# open-lab-mon-A-mini.net
KiCad netlist of a schematic drawn in EAGLE
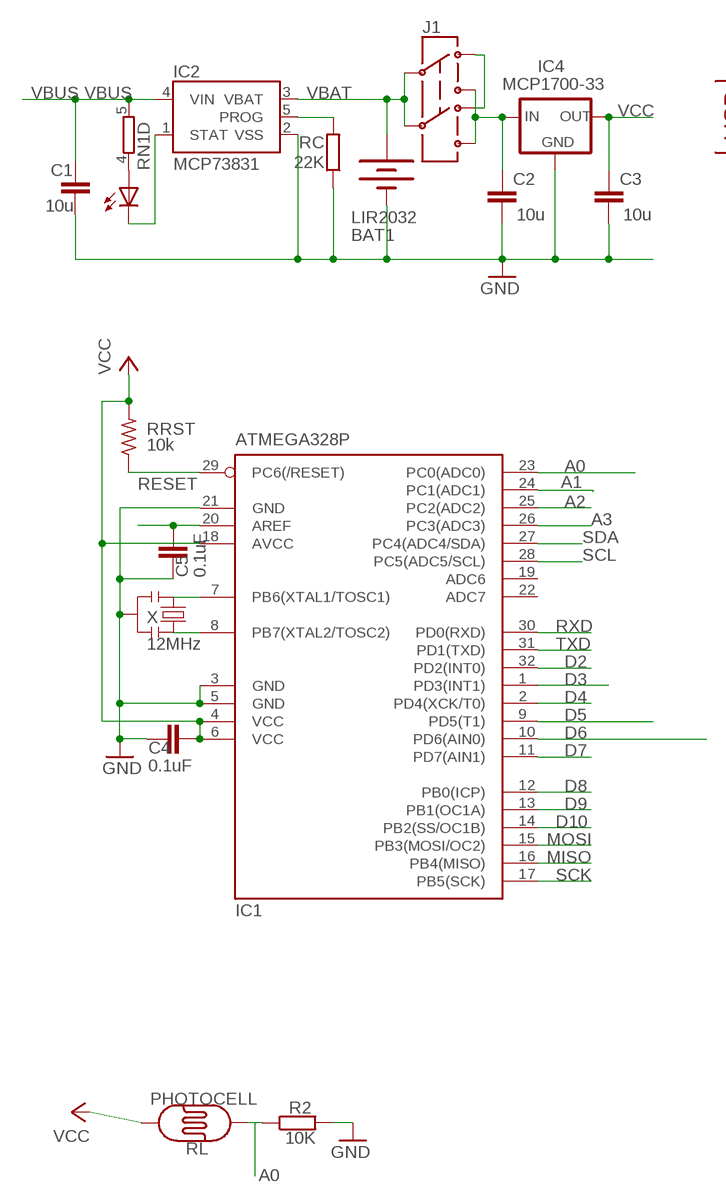
[diagram p0: schematic, sheet 1, part 1 of 2]
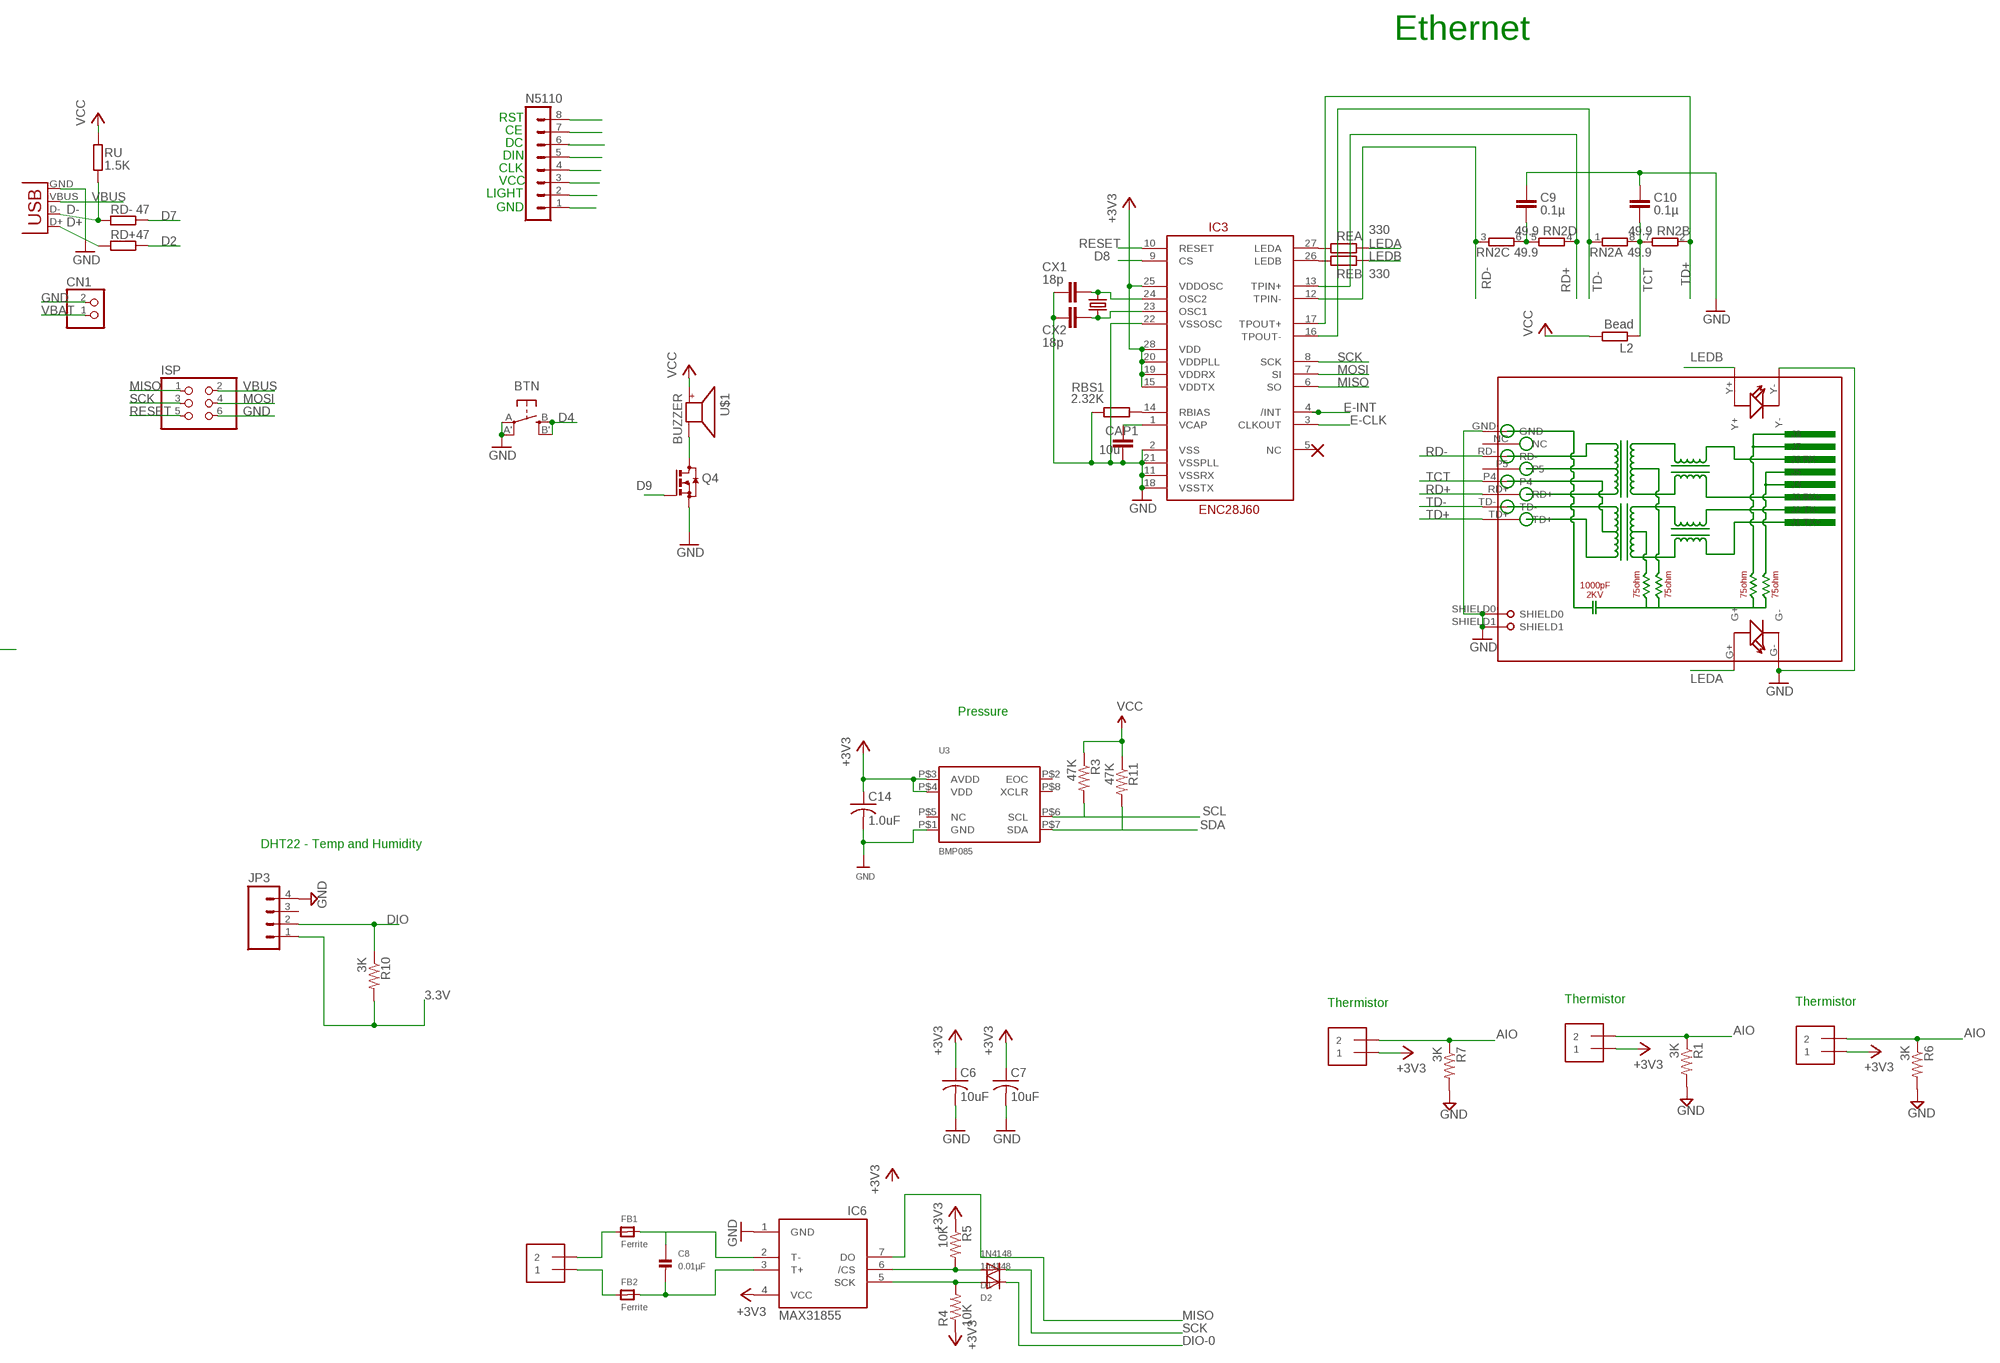
[diagram p1: schematic, sheet 1, part 2 of 2]

(export (version "E")
  (design (tool "Eeschema 10.0.6"))
  (components
    (comp (ref "BAT1")
      (value "LIR2032")
      (footprint "eagle-import:BATTCOM_20MM_PTH_SMT")
      (libsource (lib "eagle-import") (part "BATTERYBATTCOM_20MM_PTH_SMT"))
    )
    (comp (ref "BTN")
      (value "EVQQ2")
      (footprint "eagle-import:EVQ-Q2")
      (libsource (lib "eagle-import") (part "EVQQ2"))
    )
    (comp (ref "C1")
      (value "10u")
      (footprint "eagle-import:C0805")
      (libsource (lib "eagle-import") (part "resistor_C-EUC0805"))
    )
    (comp (ref "C2")
      (value "10u")
      (footprint "eagle-import:C0805")
      (libsource (lib "eagle-import") (part "resistor_C-EUC0805"))
    )
    (comp (ref "C3")
      (value "10u")
      (footprint "eagle-import:C0805")
      (libsource (lib "eagle-import") (part "resistor_C-EUC0805"))
    )
    (comp (ref "C4")
      (value "0.1uF")
      (footprint "eagle-import:C0805")
      (libsource (lib "eagle-import") (part "C-EUC0805"))
    )
    (comp (ref "C5")
      (value "0.1uF")
      (footprint "eagle-import:C0805")
      (libsource (lib "eagle-import") (part "C-EUC0805"))
    )
    (comp (ref "C6")
      (value "10uF")
      (footprint "eagle-import:C0805K")
      (libsource (lib "eagle-import") (part "C-USC0805K"))
    )
    (comp (ref "C7")
      (value "10uF")
      (footprint "eagle-import:C0805K")
      (libsource (lib "eagle-import") (part "C-USC0805K"))
    )
    (comp (ref "C8")
      (value "0.01µF")
      (footprint "eagle-import:_0805")
      (libsource (lib "eagle-import") (part "CAP_CERAMIC_0805"))
    )
    (comp (ref "C9")
      (value "0.1µ")
      (footprint "eagle-import:C0805")
      (libsource (lib "eagle-import") (part "resistor_C-EUC0805"))
    )
    (comp (ref "C10")
      (value "0.1µ")
      (footprint "eagle-import:C0805")
      (libsource (lib "eagle-import") (part "resistor_C-EUC0805"))
    )
    (comp (ref "C14")
      (value "1.0uF")
      (footprint "eagle-import:C0805")
      (libsource (lib "eagle-import") (part "C-USC0805"))
    )
    (comp (ref "CAP1")
      (value "10u")
      (footprint "eagle-import:C0805")
      (libsource (lib "eagle-import") (part "resistor_C-EUC0805"))
    )
    (comp (ref "CHG")
      (value "0805")
      (footprint "eagle-import:CHIPLED_0805")
      (libsource (lib "eagle-import") (part "LEDCHIPLED_0805"))
    )
    (comp (ref "CN1")
      (value "JST_2PIN-SMT-RA")
      (footprint "eagle-import:JST-PH-2-SMT-RA")
      (libsource (lib "eagle-import") (part "JST_2PIN-SMT-RA"))
    )
    (comp (ref "CX1")
      (value "18p")
      (footprint "eagle-import:C0805")
      (libsource (lib "eagle-import") (part "resistor_C-EUC0805"))
    )
    (comp (ref "CX2")
      (value "18p")
      (footprint "eagle-import:C0805")
      (libsource (lib "eagle-import") (part "resistor_C-EUC0805"))
    )
    (comp (ref "D1")
      (value "1N4148")
      (footprint "eagle-import:SOD-323F")
      (libsource (lib "eagle-import") (part "DIODESOD-323F"))
    )
    (comp (ref "D2")
      (value "1n4148")
      (footprint "eagle-import:SOD-323F")
      (libsource (lib "eagle-import") (part "DIODESOD-323F"))
    )
    (comp (ref "FB1")
      (value "Ferrite")
      (footprint "eagle-import:_0805")
      (libsource (lib "eagle-import") (part "FERRITE_0805"))
    )
    (comp (ref "FB2")
      (value "Ferrite")
      (footprint "eagle-import:_0805")
      (libsource (lib "eagle-import") (part "FERRITE_0805"))
    )
    (comp (ref "IC1")
      (value "ATMEGA328P")
      (footprint "eagle-import:TQFP32-08")
      (fields (field (name "MPN") "ATMEGA8-16AU"))
      (libsource (lib "eagle-import") (part "MEGA8-AI"))
    )
    (comp (ref "IC2")
      (value "MCP73831")
      (footprint "eagle-import:SOT23-5")
      (libsource (lib "eagle-import") (part "MCP73831"))
    )
    (comp (ref "IC3")
      (value "ENC28J60")
      (footprint "eagle-import:SOIC28WLONG")
      (libsource (lib "eagle-import") (part "ENC28J60SO28LONG"))
    )
    (comp (ref "IC4")
      (value "MCP1700-33")
      (footprint "eagle-import:SOT23")
      (libsource (lib "eagle-import") (part "MCP1700SOT233"))
    )
    (comp (ref "IC6")
      (value "MAX31855")
      (footprint "eagle-import:SO08")
      (libsource (lib "eagle-import") (part "MAX6675"))
    )
    (comp (ref "ISP")
      (value "PINHD-2X3")
      (footprint "eagle-import:2X03")
      (libsource (lib "eagle-import") (part "PINHD-2X3"))
    )
    (comp (ref "J1")
      (value "AYZ0202")
      (footprint "eagle-import:AYZ0202")
      (libsource (lib "eagle-import") (part "AYZ0202"))
    )
    (comp (ref "J2")
      (value "1X2-3.5MM")
      (footprint "eagle-import:1X2-3.5MM")
      (libsource (lib "eagle-import") (part "1X2-3.5MM"))
    )
    (comp (ref "J3")
      (value "1X2-3.5MM")
      (footprint "eagle-import:1X2-3.5MM")
      (libsource (lib "eagle-import") (part "1X2-3.5MM"))
    )
    (comp (ref "J4")
      (value "1X2-3.5MM")
      (footprint "eagle-import:1X2-3.5MM")
      (libsource (lib "eagle-import") (part "1X2-3.5MM"))
    )
    (comp (ref "J5")
      (value "1X2-3.5MM")
      (footprint "eagle-import:1X2-3.5MM")
      (libsource (lib "eagle-import") (part "1X2-3.5MM"))
    )
    (comp (ref "JP3")
      (value "M04LOCK")
      (footprint "eagle-import:1X04_LOCK")
      (libsource (lib "eagle-import") (part "M04LOCK"))
    )
    (comp (ref "L2")
      (value "Bead")
      (footprint "eagle-import:R0805")
      (libsource (lib "eagle-import") (part "R-EU_R0805"))
    )
    (comp (ref "N5110")
      (value "MA08-1")
      (footprint "eagle-import:MA08-1")
      (libsource (lib "eagle-import") (part "MA08-1"))
    )
    (comp (ref "Q4")
      (value "BSS123")
      (footprint "eagle-import:SOT23")
      (libsource (lib "eagle-import") (part "BSS123"))
    )
    (comp (ref "R1")
      (value "3K")
      (footprint "eagle-import:R0805")
      (libsource (lib "eagle-import") (part "R-US_R0805"))
    )
    (comp (ref "R2")
      (value "10K")
      (footprint "eagle-import:R0805")
      (libsource (lib "eagle-import") (part "R-EU_R0805"))
    )
    (comp (ref "R3")
      (value "47K")
      (footprint "eagle-import:R0805")
      (libsource (lib "eagle-import") (part "R-US_R0805"))
    )
    (comp (ref "R4")
      (value "10K")
      (footprint "eagle-import:R0805")
      (libsource (lib "eagle-import") (part "R-US_R0805"))
    )
    (comp (ref "R5")
      (value "10K")
      (footprint "eagle-import:R0805")
      (libsource (lib "eagle-import") (part "R-US_R0805"))
    )
    (comp (ref "R6")
      (value "3K")
      (footprint "eagle-import:R0805")
      (libsource (lib "eagle-import") (part "R-US_R0805"))
    )
    (comp (ref "R7")
      (value "3K")
      (footprint "eagle-import:R0805")
      (libsource (lib "eagle-import") (part "R-US_R0805"))
    )
    (comp (ref "R10")
      (value "3K")
      (footprint "eagle-import:R0805")
      (libsource (lib "eagle-import") (part "R-US_R0805"))
    )
    (comp (ref "R11")
      (value "47K")
      (footprint "eagle-import:R0805")
      (libsource (lib "eagle-import") (part "R-US_R0805"))
    )
    (comp (ref "RBS1")
      (value "2.32K")
      (footprint "eagle-import:R0805")
      (libsource (lib "eagle-import") (part "R-EU_R0805"))
    )
    (comp (ref "RC")
      (value "22K")
      (footprint "eagle-import:R0805")
      (libsource (lib "eagle-import") (part "R-EU_R0805"))
    )
    (comp (ref "RD+")
      (value "47")
      (footprint "eagle-import:R0805")
      (libsource (lib "eagle-import") (part "R-EU_R0805"))
    )
    (comp (ref "RD-")
      (value "47")
      (footprint "eagle-import:R0805")
      (libsource (lib "eagle-import") (part "R-EU_R0805"))
    )
    (comp (ref "REA")
      (value "330")
      (footprint "eagle-import:R0805")
      (libsource (lib "eagle-import") (part "R-EU_R0805"))
    )
    (comp (ref "REB")
      (value "330")
      (footprint "eagle-import:R0805")
      (libsource (lib "eagle-import") (part "R-EU_R0805"))
    )
    (comp (ref "RJ1")
      (value "HR911105A")
      (footprint "eagle-import:HR911105A")
      (libsource (lib "eagle-import") (part "HR911105A"))
    )
    (comp (ref "RL")
      (value "PHOTOCELL")
      (footprint "eagle-import:PHOTOCELL")
      (libsource (lib "eagle-import") (part "PHOTOCELLPTH"))
    )
    (comp (ref "RN1")
      (value "4R-NEXB38V")
      (footprint "eagle-import:EXB38V")
      (libsource (lib "eagle-import") (part "4R-NEXB38V"))
    )
    (comp (ref "RN2")
      (value "49.9")
      (footprint "eagle-import:EXB38V")
      (libsource (lib "eagle-import") (part "4R-NEXB38V"))
    )
    (comp (ref "RRST")
      (value "10k")
      (footprint "eagle-import:R0805@1")
      (libsource (lib "eagle-import") (part "rcl_R-US_R0805"))
    )
    (comp (ref "RU")
      (value "1.5K")
      (footprint "eagle-import:R0805")
      (libsource (lib "eagle-import") (part "R-EU_R0805"))
    )
    (comp (ref "U$1")
      (value "BUZZER")
      (footprint "eagle-import:SMT-8585-BUZZER")
      (libsource (lib "eagle-import") (part "BUZZER"))
    )
    (comp (ref "U3")
      (value "BMP085")
      (footprint "eagle-import:BMP085")
      (libsource (lib "eagle-import") (part "BMP085"))
    )
    (comp (ref "X")
      (value "12MHz")
      (footprint "eagle-import:RESONATOR-SMD")
      (libsource (lib "eagle-import") (part "RESONATORSMD"))
    )
    (comp (ref "X1")
      (value "USBSMD")
      (footprint "eagle-import:USB-MINIB")
      (libsource (lib "eagle-import") (part "USBSMD"))
    )
    (comp (ref "X2A")
      (value "25MHz")
      (footprint "eagle-import:CRYSTAL-SMD-10.5X4.8-2PIN")
      (libsource (lib "eagle-import") (part "CRYSTAL10.5X4.8"))
    )
  )
  (nets
    (net (code "1") (name "+3V3") (class "Default")
      (node (ref "C14") (pin "1") (pinfunction "1_1") (pintype "passive"))
      (node (ref "C6") (pin "1") (pinfunction "1_1") (pintype "passive"))
      (node (ref "C7") (pin "1") (pinfunction "1_1") (pintype "passive"))
      (node (ref "IC3") (pin "15") (pinfunction "VDDTX_15") (pintype "bidirectional"))
      (node (ref "IC3") (pin "19") (pinfunction "VDDRX_19") (pintype "bidirectional"))
      (node (ref "IC3") (pin "20") (pinfunction "VDDPLL_20") (pintype "bidirectional"))
      (node (ref "IC3") (pin "25") (pinfunction "VDDOSC_25") (pintype "bidirectional"))
      (node (ref "IC3") (pin "28") (pinfunction "VDD_28") (pintype "bidirectional"))
      (node (ref "IC6") (pin "4") (pinfunction "VCC_4") (pintype "power_in"))
      (node (ref "J3") (pin "1") (pinfunction "1_1") (pintype "passive"))
      (node (ref "J4") (pin "1") (pinfunction "1_1") (pintype "passive"))
      (node (ref "J5") (pin "1") (pinfunction "1_1") (pintype "passive"))
      (node (ref "R4") (pin "1") (pinfunction "1_1") (pintype "passive"))
      (node (ref "R5") (pin "1") (pinfunction "1_1") (pintype "passive"))
      (node (ref "U3") (pin "P$3") (pinfunction "AVDD_P$3") (pintype "bidirectional"))
      (node (ref "U3") (pin "P$4") (pinfunction "VDD_P$4") (pintype "bidirectional"))
    )
    (net (code "2") (name "/3.3V") (class "Default")
      (node (ref "JP3") (pin "1") (pinfunction "1_1") (pintype "passive"))
      (node (ref "R10") (pin "2") (pinfunction "2_2") (pintype "passive"))
    )
    (net (code "3") (name "/A0") (class "Default")
      (node (ref "IC1") (pin "23") (pinfunction "PC0(ADC0)_23") (pintype "bidirectional"))
      (node (ref "R2") (pin "1") (pinfunction "1_1") (pintype "passive"))
      (node (ref "RL") (pin "1") (pinfunction "P$1_1") (pintype "bidirectional"))
    )
    (net (code "4") (name "/A1") (class "Default")
      (node (ref "IC1") (pin "24") (pinfunction "PC1(ADC1)_24") (pintype "bidirectional"))
    )
    (net (code "5") (name "/A2") (class "Default")
      (node (ref "IC1") (pin "25") (pinfunction "PC2(ADC2)_25") (pintype "bidirectional"))
    )
    (net (code "6") (name "/A3") (class "Default")
      (node (ref "IC1") (pin "26") (pinfunction "PC3(ADC3)_26") (pintype "bidirectional"))
    )
    (net (code "7") (name "/AIO") (class "Default")
      (node (ref "J3") (pin "2") (pinfunction "2_2") (pintype "passive"))
      (node (ref "J4") (pin "2") (pinfunction "2_2") (pintype "passive"))
      (node (ref "J5") (pin "2") (pinfunction "2_2") (pintype "passive"))
      (node (ref "R1") (pin "1") (pinfunction "1_1") (pintype "passive"))
      (node (ref "R6") (pin "1") (pinfunction "1_1") (pintype "passive"))
      (node (ref "R7") (pin "1") (pinfunction "1_1") (pintype "passive"))
    )
    (net (code "8") (name "/D+") (class "Default")
      (node (ref "RD+") (pin "1") (pinfunction "1_1") (pintype "passive"))
      (node (ref "X1") (pin "D+") (pinfunction "D+_D+") (pintype "bidirectional"))
    )
    (net (code "9") (name "/D-") (class "Default")
      (node (ref "RD-") (pin "1") (pinfunction "1_1") (pintype "passive"))
      (node (ref "RU") (pin "1") (pinfunction "1_1") (pintype "passive"))
      (node (ref "X1") (pin "D-") (pinfunction "D-_D-") (pintype "bidirectional"))
    )
    (net (code "10") (name "/D2") (class "Default")
      (node (ref "IC1") (pin "32") (pinfunction "PD2(INT0)_32") (pintype "bidirectional"))
      (node (ref "RD+") (pin "2") (pinfunction "2_2") (pintype "passive"))
    )
    (net (code "11") (name "/D3") (class "Default")
      (node (ref "IC1") (pin "1") (pinfunction "PD3(INT1)_1") (pintype "bidirectional"))
    )
    (net (code "12") (name "/D4") (class "Default")
      (node (ref "BTN") (pin "B") (pinfunction "S_B") (pintype "passive"))
      (node (ref "BTN") (pin "B'") (pinfunction "S1_B'") (pintype "passive"))
      (node (ref "IC1") (pin "2") (pinfunction "PD4(XCK/T0)_2") (pintype "bidirectional"))
    )
    (net (code "13") (name "/D5") (class "Default")
      (node (ref "IC1") (pin "9") (pinfunction "PD5(T1)_9") (pintype "bidirectional"))
    )
    (net (code "14") (name "/D6") (class "Default")
      (node (ref "IC1") (pin "10") (pinfunction "PD6(AIN0)_10") (pintype "bidirectional"))
    )
    (net (code "15") (name "/D7") (class "Default")
      (node (ref "IC1") (pin "11") (pinfunction "PD7(AIN1)_11") (pintype "bidirectional"))
      (node (ref "RD-") (pin "2") (pinfunction "2_2") (pintype "passive"))
    )
    (net (code "16") (name "/D8") (class "Default")
      (node (ref "IC1") (pin "12") (pinfunction "PB0(ICP)_12") (pintype "bidirectional"))
      (node (ref "IC3") (pin "9") (pinfunction "CS_9") (pintype "bidirectional"))
    )
    (net (code "17") (name "/D9") (class "Default")
      (node (ref "IC1") (pin "13") (pinfunction "PB1(OC1A)_13") (pintype "bidirectional"))
      (node (ref "Q4") (pin "1") (pinfunction "G_1") (pintype "passive"))
    )
    (net (code "18") (name "/D10") (class "Default")
      (node (ref "IC1") (pin "14") (pinfunction "PB2(SS/OC1B)_14") (pintype "bidirectional"))
    )
    (net (code "19") (name "/DIO") (class "Default")
      (node (ref "JP3") (pin "2") (pinfunction "2_2") (pintype "passive"))
      (node (ref "R10") (pin "1") (pinfunction "1_1") (pintype "passive"))
    )
    (net (code "20") (name "/DIO-0") (class "Default")
      (node (ref "D2") (pin "C") (pinfunction "C_C") (pintype "passive"))
    )
    (net (code "21") (name "/E-CLK") (class "Default")
      (node (ref "IC3") (pin "3") (pinfunction "CLKOUT_3") (pintype "bidirectional"))
    )
    (net (code "22") (name "/E-INT") (class "Default")
      (node (ref "IC3") (pin "4") (pinfunction "/INT_4") (pintype "bidirectional"))
    )
    (net (code "23") (name "/LEDA") (class "Default")
      (node (ref "REA") (pin "2") (pinfunction "2_2") (pintype "passive"))
      (node (ref "RJ1") (pin "G+") (pinfunction "G+_G+") (pintype "bidirectional"))
    )
    (net (code "24") (name "/LEDB") (class "Default")
      (node (ref "REB") (pin "2") (pinfunction "2_2") (pintype "passive"))
      (node (ref "RJ1") (pin "Y+") (pinfunction "Y+_Y+") (pintype "bidirectional"))
    )
    (net (code "25") (name "/MISO") (class "Default")
      (node (ref "IC1") (pin "16") (pinfunction "PB4(MISO)_16") (pintype "bidirectional"))
      (node (ref "IC3") (pin "6") (pinfunction "SO_6") (pintype "bidirectional"))
      (node (ref "IC6") (pin "7") (pinfunction "DO_7") (pintype "output"))
      (node (ref "ISP") (pin "1") (pinfunction "1_1") (pintype "passive"))
    )
    (net (code "26") (name "/MOSI") (class "Default")
      (node (ref "IC1") (pin "15") (pinfunction "PB3(MOSI/OC2)_15") (pintype "bidirectional"))
      (node (ref "IC3") (pin "7") (pinfunction "SI_7") (pintype "bidirectional"))
      (node (ref "ISP") (pin "4") (pinfunction "4_4") (pintype "passive"))
    )
    (net (code "27") (name "/RD+") (class "Default")
      (node (ref "IC3") (pin "13") (pinfunction "TPIN+_13") (pintype "bidirectional"))
      (node (ref "RJ1") (pin "RD+") (pinfunction "RD+_RD+") (pintype "bidirectional"))
      (node (ref "RN2") (pin "4") (pinfunction "1_4") (pintype "passive"))
    )
    (net (code "28") (name "/RD-") (class "Default")
      (node (ref "IC3") (pin "12") (pinfunction "TPIN-_12") (pintype "bidirectional"))
      (node (ref "RJ1") (pin "RD-") (pinfunction "RD-_RD-") (pintype "bidirectional"))
      (node (ref "RN2") (pin "3") (pinfunction "1_3") (pintype "passive"))
    )
    (net (code "29") (name "/RESET") (class "Default")
      (node (ref "IC1") (pin "29") (pinfunction "PC6(/RESET)_29") (pintype "bidirectional"))
      (node (ref "IC3") (pin "10") (pinfunction "RESET_10") (pintype "bidirectional"))
      (node (ref "ISP") (pin "5") (pinfunction "5_5") (pintype "passive"))
      (node (ref "RRST") (pin "1") (pinfunction "1_1") (pintype "passive"))
    )
    (net (code "30") (name "/RXD") (class "Default")
      (node (ref "IC1") (pin "30") (pinfunction "PD0(RXD)_30") (pintype "bidirectional"))
    )
    (net (code "31") (name "/SCK") (class "Default")
      (node (ref "D1") (pin "C") (pinfunction "C_C") (pintype "passive"))
      (node (ref "IC1") (pin "17") (pinfunction "PB5(SCK)_17") (pintype "bidirectional"))
      (node (ref "IC3") (pin "8") (pinfunction "SCK_8") (pintype "bidirectional"))
      (node (ref "ISP") (pin "3") (pinfunction "3_3") (pintype "passive"))
    )
    (net (code "32") (name "/SCL") (class "Default")
      (node (ref "IC1") (pin "28") (pinfunction "PC5(ADC5/SCL)_28") (pintype "bidirectional"))
      (node (ref "U3") (pin "P$6") (pinfunction "SCL_P$6") (pintype "bidirectional"))
    )
    (net (code "33") (name "/SDA") (class "Default")
      (node (ref "IC1") (pin "27") (pinfunction "PC4(ADC4/SDA)_27") (pintype "bidirectional"))
      (node (ref "U3") (pin "P$7") (pinfunction "SDA_P$7") (pintype "bidirectional"))
    )
    (net (code "34") (name "/TCT") (class "Default")
      (node (ref "C10") (pin "2") (pinfunction "2_2") (pintype "passive"))
      (node (ref "L2") (pin "1") (pinfunction "1_1") (pintype "passive"))
      (node (ref "RJ1") (pin "P4") (pinfunction "P4_P4") (pintype "bidirectional"))
      (node (ref "RN2") (pin "7") (pinfunction "2_7") (pintype "passive"))
      (node (ref "RN2") (pin "8") (pinfunction "2_8") (pintype "passive"))
    )
    (net (code "35") (name "/TD+") (class "Default")
      (node (ref "IC3") (pin "17") (pinfunction "TPOUT+_17") (pintype "bidirectional"))
      (node (ref "RJ1") (pin "TD+") (pinfunction "TD+_TD+") (pintype "bidirectional"))
      (node (ref "RN2") (pin "2") (pinfunction "1_2") (pintype "passive"))
    )
    (net (code "36") (name "/TD-") (class "Default")
      (node (ref "IC3") (pin "16") (pinfunction "TPOUT-_16") (pintype "bidirectional"))
      (node (ref "RJ1") (pin "TD-") (pinfunction "TD-_TD-") (pintype "bidirectional"))
      (node (ref "RN2") (pin "1") (pinfunction "1_1") (pintype "passive"))
    )
    (net (code "37") (name "/TXD") (class "Default")
      (node (ref "IC1") (pin "31") (pinfunction "PD1(TXD)_31") (pintype "bidirectional"))
    )
    (net (code "38") (name "/VBAT") (class "Default")
      (node (ref "BAT1") (pin "P$2") (pinfunction "+_P$2") (pintype "power_in"))
      (node (ref "CN1") (pin "1") (pinfunction "2_1") (pintype "passive"))
      (node (ref "IC2") (pin "3") (pinfunction "VBAT_3") (pintype "power_in"))
      (node (ref "J1") (pin "2") (pinfunction "2_2") (pintype "bidirectional"))
      (node (ref "J1") (pin "5") (pinfunction "5_5") (pintype "bidirectional"))
    )
    (net (code "39") (name "/VBUS") (class "Default")
      (node (ref "C1") (pin "1") (pinfunction "1_1") (pintype "passive"))
      (node (ref "IC2") (pin "4") (pinfunction "VIN_4") (pintype "power_in"))
      (node (ref "ISP") (pin "2") (pinfunction "2_2") (pintype "passive"))
      (node (ref "RN1") (pin "5") (pinfunction "2_5") (pintype "passive"))
      (node (ref "X1") (pin "VBUS") (pinfunction "VBUS_VBUS") (pintype "bidirectional"))
    )
    (net (code "40") (name "GND") (class "Default")
      (node (ref "BAT1") (pin "P$1") (pinfunction "-_P$1") (pintype "power_in"))
      (node (ref "BTN") (pin "A") (pinfunction "P_A") (pintype "passive"))
      (node (ref "BTN") (pin "A'") (pinfunction "P1_A'") (pintype "passive"))
      (node (ref "C1") (pin "2") (pinfunction "2_2") (pintype "passive"))
      (node (ref "C10") (pin "1") (pinfunction "1_1") (pintype "passive"))
      (node (ref "C14") (pin "2") (pinfunction "2_2") (pintype "passive"))
      (node (ref "C2") (pin "2") (pinfunction "2_2") (pintype "passive"))
      (node (ref "C3") (pin "2") (pinfunction "2_2") (pintype "passive"))
      (node (ref "C4") (pin "1") (pinfunction "1_1") (pintype "passive"))
      (node (ref "C5") (pin "1") (pinfunction "1_1") (pintype "passive"))
      (node (ref "C6") (pin "2") (pinfunction "2_2") (pintype "passive"))
      (node (ref "C7") (pin "2") (pinfunction "2_2") (pintype "passive"))
      (node (ref "C9") (pin "1") (pinfunction "1_1") (pintype "passive"))
      (node (ref "CAP1") (pin "2") (pinfunction "2_2") (pintype "passive"))
      (node (ref "CN1") (pin "2") (pinfunction "1_2") (pintype "passive"))
      (node (ref "CX1") (pin "2") (pinfunction "2_2") (pintype "passive"))
      (node (ref "CX2") (pin "2") (pinfunction "2_2") (pintype "passive"))
      (node (ref "IC1") (pin "21") (pinfunction "GND_21") (pintype "power_in"))
      (node (ref "IC1") (pin "3") (pinfunction "GND_3") (pintype "power_in"))
      (node (ref "IC1") (pin "5") (pinfunction "GND_5") (pintype "power_in"))
      (node (ref "IC2") (pin "2") (pinfunction "VSS_2") (pintype "power_in"))
      (node (ref "IC3") (pin "11") (pinfunction "VSSRX_11") (pintype "bidirectional"))
      (node (ref "IC3") (pin "18") (pinfunction "VSSTX_18") (pintype "bidirectional"))
      (node (ref "IC3") (pin "2") (pinfunction "VSS_2") (pintype "bidirectional"))
      (node (ref "IC3") (pin "21") (pinfunction "VSSPLL_21") (pintype "bidirectional"))
      (node (ref "IC3") (pin "22") (pinfunction "VSSOSC_22") (pintype "bidirectional"))
      (node (ref "IC4") (pin "1") (pinfunction "GND_1") (pintype "input"))
      (node (ref "IC6") (pin "1") (pinfunction "GND_1") (pintype "power_in"))
      (node (ref "ISP") (pin "6") (pinfunction "6_6") (pintype "passive"))
      (node (ref "JP3") (pin "4") (pinfunction "4_4") (pintype "passive"))
      (node (ref "Q4") (pin "2") (pinfunction "S_2") (pintype "passive"))
      (node (ref "R1") (pin "2") (pinfunction "2_2") (pintype "passive"))
      (node (ref "R2") (pin "2") (pinfunction "2_2") (pintype "passive"))
      (node (ref "R6") (pin "2") (pinfunction "2_2") (pintype "passive"))
      (node (ref "R7") (pin "2") (pinfunction "2_2") (pintype "passive"))
      (node (ref "RBS1") (pin "1") (pinfunction "1_1") (pintype "passive"))
      (node (ref "RC") (pin "1") (pinfunction "1_1") (pintype "passive"))
      (node (ref "RJ1") (pin "G-") (pinfunction "G-_G-") (pintype "bidirectional"))
      (node (ref "RJ1") (pin "GND") (pinfunction "GND_GND") (pintype "bidirectional"))
      (node (ref "RJ1") (pin "SHIELD0") (pinfunction "SHIELD0_SHIELD0") (pintype "bidirectional"))
      (node (ref "RJ1") (pin "SHIELD1") (pinfunction "SHIELD1_SHIELD1") (pintype "bidirectional"))
      (node (ref "RJ1") (pin "Y-") (pinfunction "Y-_Y-") (pintype "bidirectional"))
      (node (ref "U3") (pin "P$1") (pinfunction "GND_P$1") (pintype "bidirectional"))
      (node (ref "X") (pin "2") (pinfunction "2_2") (pintype "passive"))
      (node (ref "X1") (pin "GND") (pinfunction "GND_GND") (pintype "bidirectional"))
    )
    (net (code "41") (name "Net-(C8-P$1)") (class "Default")
      (node (ref "C8") (pin "1") (pinfunction "P$1_1") (pintype "passive"))
      (node (ref "FB1") (pin "2") (pinfunction "P$2_2") (pintype "passive"))
      (node (ref "IC6") (pin "2") (pinfunction "T-_2") (pintype "input"))
    )
    (net (code "42") (name "Net-(C8-P$2)") (class "Default")
      (node (ref "C8") (pin "2") (pinfunction "P$2_2") (pintype "passive"))
      (node (ref "FB2") (pin "2") (pinfunction "P$2_2") (pintype "passive"))
      (node (ref "IC6") (pin "3") (pinfunction "T+_3") (pintype "input"))
    )
    (net (code "43") (name "Net-(FB1-P$1)") (class "Default")
      (node (ref "FB1") (pin "1") (pinfunction "P$1_1") (pintype "passive"))
      (node (ref "J2") (pin "2") (pinfunction "2_2") (pintype "passive"))
    )
    (net (code "44") (name "Net-(FB2-P$1)") (class "Default")
      (node (ref "FB2") (pin "1") (pinfunction "P$1_1") (pintype "passive"))
      (node (ref "J2") (pin "1") (pinfunction "1_1") (pintype "passive"))
    )
    (net (code "45") (name "Net-(IC1-AREF)") (class "Default")
      (node (ref "C5") (pin "2") (pinfunction "2_2") (pintype "passive"))
      (node (ref "IC1") (pin "20") (pinfunction "AREF_20") (pintype "passive"))
    )
    (net (code "46") (name "Net-(IC1-PB6(XTAL1{slash}TOSC1))") (class "Default")
      (node (ref "IC1") (pin "7") (pinfunction "PB6(XTAL1/TOSC1)_7") (pintype "bidirectional"))
      (node (ref "X") (pin "1") (pinfunction "1_1") (pintype "passive"))
    )
    (net (code "47") (name "Net-(IC1-PB7(XTAL2{slash}TOSC2))") (class "Default")
      (node (ref "IC1") (pin "8") (pinfunction "PB7(XTAL2/TOSC2)_8") (pintype "bidirectional"))
      (node (ref "X") (pin "3") (pinfunction "3_3") (pintype "passive"))
    )
    (net (code "48") (name "Net-(IC2-PROG)") (class "Default")
      (node (ref "IC2") (pin "5") (pinfunction "PROG_5") (pintype "input"))
      (node (ref "RC") (pin "2") (pinfunction "2_2") (pintype "passive"))
    )
    (net (code "49") (name "Net-(IC2-STAT)") (class "Default")
      (node (ref "CHG") (pin "C") (pinfunction "C_C") (pintype "passive"))
      (node (ref "IC2") (pin "1") (pinfunction "STAT_1") (pintype "output"))
    )
    (net (code "50") (name "Net-(IC3-LEDA)") (class "Default")
      (node (ref "IC3") (pin "27") (pinfunction "LEDA_27") (pintype "bidirectional"))
      (node (ref "REA") (pin "1") (pinfunction "1_1") (pintype "passive"))
    )
    (net (code "51") (name "Net-(IC3-LEDB)") (class "Default")
      (node (ref "IC3") (pin "26") (pinfunction "LEDB_26") (pintype "bidirectional"))
      (node (ref "REB") (pin "1") (pinfunction "1_1") (pintype "passive"))
    )
    (net (code "52") (name "Net-(IC3-OSC1)") (class "Default")
      (node (ref "CX2") (pin "1") (pinfunction "1_1") (pintype "passive"))
      (node (ref "IC3") (pin "23") (pinfunction "OSC1_23") (pintype "bidirectional"))
      (node (ref "X2A") (pin "P$1") (pinfunction "1_P$1") (pintype "passive"))
    )
    (net (code "53") (name "Net-(IC3-OSC2)") (class "Default")
      (node (ref "CX1") (pin "1") (pinfunction "1_1") (pintype "passive"))
      (node (ref "IC3") (pin "24") (pinfunction "OSC2_24") (pintype "bidirectional"))
      (node (ref "X2A") (pin "P$2") (pinfunction "2_P$2") (pintype "passive"))
    )
    (net (code "54") (name "Net-(IC3-RBIAS)") (class "Default")
      (node (ref "IC3") (pin "14") (pinfunction "RBIAS_14") (pintype "bidirectional"))
      (node (ref "RBS1") (pin "2") (pinfunction "2_2") (pintype "passive"))
    )
    (net (code "55") (name "Net-(IC3-VCAP)") (class "Default")
      (node (ref "CAP1") (pin "1") (pinfunction "1_1") (pintype "passive"))
      (node (ref "IC3") (pin "1") (pinfunction "VCAP_1") (pintype "bidirectional"))
    )
    (net (code "56") (name "Net-(IC4-IN)") (class "Default")
      (node (ref "C2") (pin "1") (pinfunction "1_1") (pintype "passive"))
      (node (ref "IC4") (pin "3") (pinfunction "IN_3") (pintype "input"))
      (node (ref "J1") (pin "1") (pinfunction "3_1") (pintype "bidirectional"))
      (node (ref "J1") (pin "4") (pinfunction "6_4") (pintype "bidirectional"))
    )
    (net (code "57") (name "Net-(IC6-SCK)") (class "Default")
      (node (ref "D2") (pin "A") (pinfunction "A_A") (pintype "passive"))
      (node (ref "IC6") (pin "5") (pinfunction "SCK_5") (pintype "input"))
      (node (ref "R4") (pin "2") (pinfunction "2_2") (pintype "passive"))
    )
    (net (code "58") (name "Net-(IC6-{slash}CS)") (class "Default")
      (node (ref "D1") (pin "A") (pinfunction "A_A") (pintype "passive"))
      (node (ref "IC6") (pin "6") (pinfunction "/CS_6") (pintype "input"))
      (node (ref "R5") (pin "2") (pinfunction "2_2") (pintype "passive"))
    )
    (net (code "59") (name "Net-(J1-1)") (class "Default")
      (node (ref "J1") (pin "3") (pinfunction "1_3") (pintype "bidirectional"))
      (node (ref "J1") (pin "6") (pinfunction "4_6") (pintype "bidirectional"))
    )
    (net (code "60") (name "Net-(Q4-D)") (class "Default")
      (node (ref "Q4") (pin "3") (pinfunction "D_3") (pintype "passive"))
      (node (ref "U$1") (pin "-") (pinfunction "-_-") (pintype "passive"))
    )
    (net (code "61") (name "Net-(RN1D-1)") (class "Default")
      (node (ref "CHG") (pin "A") (pinfunction "A_A") (pintype "passive"))
      (node (ref "RN1") (pin "4") (pinfunction "1_4") (pintype "passive"))
    )
    (net (code "62") (name "Net-(RN2C-2)") (class "Default")
      (node (ref "C9") (pin "2") (pinfunction "2_2") (pintype "passive"))
      (node (ref "RN2") (pin "5") (pinfunction "2_5") (pintype "passive"))
      (node (ref "RN2") (pin "6") (pinfunction "2_6") (pintype "passive"))
    )
    (net (code "63") (name "VCC") (class "Default")
      (node (ref "C3") (pin "1") (pinfunction "1_1") (pintype "passive"))
      (node (ref "C4") (pin "2") (pinfunction "2_2") (pintype "passive"))
      (node (ref "IC1") (pin "18") (pinfunction "AVCC_18") (pintype "power_in"))
      (node (ref "IC1") (pin "4") (pinfunction "VCC_4") (pintype "power_in"))
      (node (ref "IC1") (pin "6") (pinfunction "VCC_6") (pintype "power_in"))
      (node (ref "IC4") (pin "2") (pinfunction "OUT_2") (pintype "passive"))
      (node (ref "L2") (pin "2") (pinfunction "2_2") (pintype "passive"))
      (node (ref "R11") (pin "1") (pinfunction "1_1") (pintype "passive"))
      (node (ref "R3") (pin "1") (pinfunction "1_1") (pintype "passive"))
      (node (ref "RL") (pin "2") (pinfunction "P$2_2") (pintype "bidirectional"))
      (node (ref "RRST") (pin "2") (pinfunction "2_2") (pintype "passive"))
      (node (ref "RU") (pin "2") (pinfunction "2_2") (pintype "passive"))
      (node (ref "U$1") (pin "+") (pinfunction "+_+") (pintype "passive"))
    )
    (net (code "64") (name "unconnected-(IC1-ADC6-Pad19)") (class "Default")
      (node (ref "IC1") (pin "19") (pinfunction "ADC6_19") (pintype "bidirectional"))
    )
    (net (code "65") (name "unconnected-(IC1-ADC7-Pad22)") (class "Default")
      (node (ref "IC1") (pin "22") (pinfunction "ADC7_22") (pintype "bidirectional"))
    )
    (net (code "66") (name "unconnected-(IC3-NC-Pad5)") (class "Default")
      (node (ref "IC3") (pin "5") (pinfunction "NC_5") (pintype "bidirectional"))
    )
    (net (code "67") (name "unconnected-(JP3-Pad3)") (class "Default")
      (node (ref "JP3") (pin "3") (pinfunction "3_3") (pintype "passive"))
    )
    (net (code "68") (name "unconnected-(N5110-Pad1)") (class "Default")
      (node (ref "N5110") (pin "1") (pinfunction "1_1") (pintype "passive"))
    )
    (net (code "69") (name "unconnected-(N5110-Pad2)") (class "Default")
      (node (ref "N5110") (pin "2") (pinfunction "2_2") (pintype "passive"))
    )
    (net (code "70") (name "unconnected-(N5110-Pad3)") (class "Default")
      (node (ref "N5110") (pin "3") (pinfunction "3_3") (pintype "passive"))
    )
    (net (code "71") (name "unconnected-(N5110-Pad4)") (class "Default")
      (node (ref "N5110") (pin "4") (pinfunction "4_4") (pintype "passive"))
    )
    (net (code "72") (name "unconnected-(N5110-Pad5)") (class "Default")
      (node (ref "N5110") (pin "5") (pinfunction "5_5") (pintype "passive"))
    )
    (net (code "73") (name "unconnected-(N5110-Pad6)") (class "Default")
      (node (ref "N5110") (pin "6") (pinfunction "6_6") (pintype "passive"))
    )
    (net (code "74") (name "unconnected-(N5110-Pad7)") (class "Default")
      (node (ref "N5110") (pin "7") (pinfunction "7_7") (pintype "passive"))
    )
    (net (code "75") (name "unconnected-(N5110-Pad8)") (class "Default")
      (node (ref "N5110") (pin "8") (pinfunction "8_8") (pintype "passive"))
    )
    (net (code "76") (name "unconnected-(R3-Pad2)") (class "Default")
      (node (ref "R3") (pin "2") (pinfunction "2_2") (pintype "passive"))
    )
    (net (code "77") (name "unconnected-(R11-Pad2)") (class "Default")
      (node (ref "R11") (pin "2") (pinfunction "2_2") (pintype "passive"))
    )
    (net (code "78") (name "unconnected-(RJ1-PadNC)") (class "Default")
      (node (ref "RJ1") (pin "NC") (pinfunction "NC_NC") (pintype "bidirectional"))
    )
    (net (code "79") (name "unconnected-(RJ1-PadP5)") (class "Default")
      (node (ref "RJ1") (pin "P5") (pinfunction "P5_P5") (pintype "bidirectional"))
    )
    (net (code "80") (name "unconnected-(U3-EOC-PadP$2)") (class "Default")
      (node (ref "U3") (pin "P$2") (pinfunction "EOC_P$2") (pintype "bidirectional"))
    )
    (net (code "81") (name "unconnected-(U3-NC-PadP$5)") (class "Default")
      (node (ref "U3") (pin "P$5") (pinfunction "NC_P$5") (pintype "bidirectional"))
    )
    (net (code "82") (name "unconnected-(U3-XCLR-PadP$8)") (class "Default")
      (node (ref "U3") (pin "P$8") (pinfunction "XCLR_P$8") (pintype "bidirectional"))
    )
  )
)
